# Jetson-CAN-Transceiver.net
KiCad netlist of a schematic drawn in Altium Designer
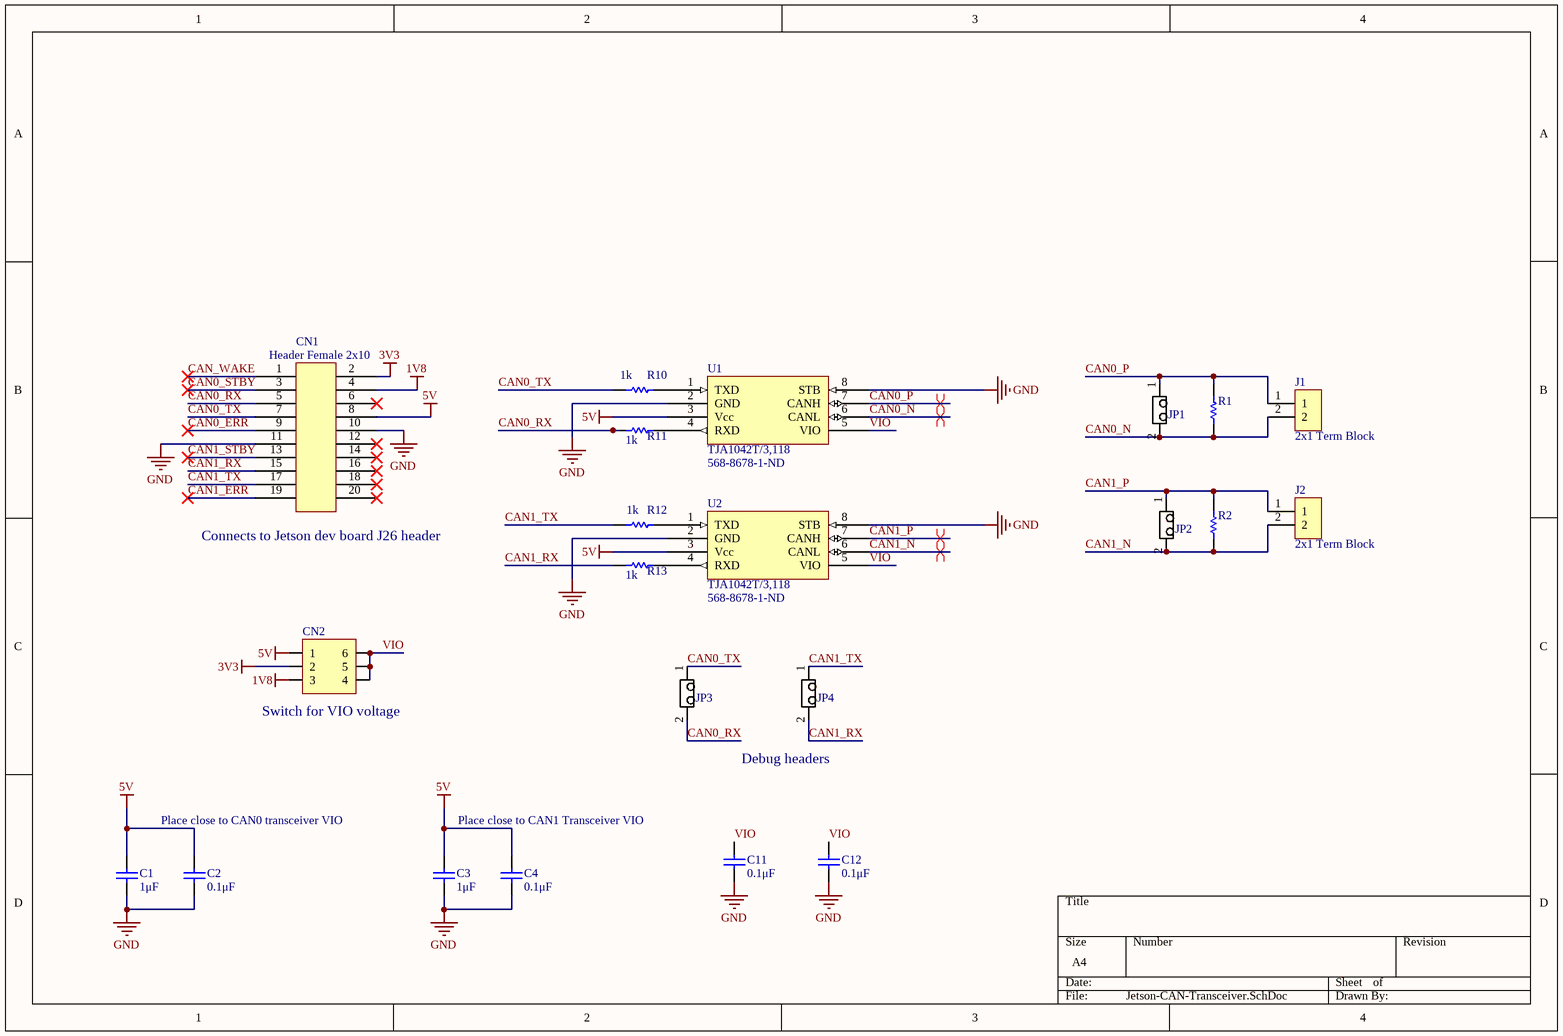
[diagram p0: Jetson-CAN-Transceiver.SchDoc]

(export (version "E")
  (design (tool "Eeschema 10.0.6"))
  (components
    (comp (ref "C1")
      (value "1μF")
      (footprint "CAPC1608N(0603\")")
      (description "Capacitor, Ceramic, 50V, +/- 10%, 0603 SMD, X5R")
      (fields (field (name "CREATED BY") "Lyden Smith"))
      (libsource (lib "AUVic_Integrated_Library_Capacitors") (part "1uF 50V 0603 SMD, Ceramic"))
    )
    (comp (ref "C2")
      (value "0.1μF")
      (footprint "CAPC1608N(0603\")")
      (description "Capacitor, Ceramic, 16V, +/- 10%, 0603 SMD, X7R")
      (fields (field (name "PUBLISHER") "AUVic") (field (name "CREATED BY") "Andy Bates"))
      (libsource (lib "AUVic_Integrated_Library_Capacitors") (part "0.1uF 16V 0603 SMD, Ceramic"))
    )
    (comp (ref "C3")
      (value "1μF")
      (footprint "CAPC1608N(0603\")")
      (description "Capacitor, Ceramic, 50V, +/- 10%, 0603 SMD, X5R")
      (fields (field (name "CREATED BY") "Lyden Smith"))
      (libsource (lib "AUVic_Integrated_Library_Capacitors") (part "1uF 50V 0603 SMD, Ceramic"))
    )
    (comp (ref "C4")
      (value "0.1μF")
      (footprint "CAPC1608N(0603\")")
      (description "Capacitor, Ceramic, 16V, +/- 10%, 0603 SMD, X7R")
      (fields (field (name "PUBLISHER") "AUVic") (field (name "CREATED BY") "Andy Bates"))
      (libsource (lib "AUVic_Integrated_Library_Capacitors") (part "0.1uF 16V 0603 SMD, Ceramic"))
    )
    (comp (ref "C11")
      (value "0.1μF")
      (footprint "CAPC1608N(0603\")")
      (description "Capacitor, Ceramic, 16V, +/- 10%, 0603 SMD, X7R")
      (fields (field (name "PUBLISHER") "AUVic") (field (name "CREATED BY") "Andy Bates"))
      (libsource (lib "AUVic_Integrated_Library_Capacitors") (part "0.1uF 16V 0603 SMD, Ceramic"))
    )
    (comp (ref "C12")
      (value "0.1μF")
      (footprint "CAPC1608N(0603\")")
      (description "Capacitor, Ceramic, 16V, +/- 10%, 0603 SMD, X7R")
      (fields (field (name "PUBLISHER") "AUVic") (field (name "CREATED BY") "Andy Bates"))
      (libsource (lib "AUVic_Integrated_Library_Capacitors") (part "0.1uF 16V 0603 SMD, Ceramic"))
    )
    (comp (ref "CN1")
      (value "Header Female 2x10")
      (footprint "HEADER, FEMALE/MALE, 2x10, 100mil")
      (description "Header, Female with extended Male pins, 2x10, THT, 100mil")
      (fields (field (name "CREATED BY") "Poorna Chander Kalidas"))
      (libsource (lib "AUVic_Integrated_Library_Connectors") (part "Header, Female/Male, 2x10, THT, 100mil"))
    )
    (comp (ref "CN2")
      (value "Header, Male, 2x3, Pitch: 0.1\" (2.54mm), THT")
      (footprint "Header, Male, 2x3, Pitch: 0.1\" (2.54mm),THT")
      (fields
        (field (name "PUBLISHER") "AUVic")
        (field (name "REVIEWED BY") "*")
        (field (name "CREATED BY") "Andy Bates")
      )
      (libsource (lib "AUVic_Integrated_Library_Connectors") (part "Header, Male, 2x3, Pitch{colon} 0.1{dblquote} (2.54mm), THT"))
    )
    (comp (ref "J1")
      (value "2x1 Term Block")
      (footprint "2X1 Terminal Blocks")
      (fields (field (name "MADE BY") "Andy Bates"))
      (libsource (lib "AUVic_Integrated_Library_Connectors") (part "2x1 Terminal Block"))
    )
    (comp (ref "J2")
      (value "2x1 Term Block")
      (footprint "2X1 Terminal Blocks")
      (fields (field (name "MADE BY") "Andy Bates"))
      (libsource (lib "AUVic_Integrated_Library_Connectors") (part "2x1 Terminal Block"))
    )
    (comp (ref "JP1")
      (value "1X2 Pin Head")
      (footprint "2X1 Males Header")
      (fields (field (name "MADE BY") "Andy Bates"))
      (libsource (lib "AUVic_Integrated_Library_Connectors") (part "1x2 Male Header"))
    )
    (comp (ref "JP2")
      (value "1X2 Pin Head")
      (footprint "2X1 Males Header")
      (fields (field (name "MADE BY") "Andy Bates"))
      (libsource (lib "AUVic_Integrated_Library_Connectors") (part "1x2 Male Header"))
    )
    (comp (ref "JP3")
      (value "1X2 Pin Head")
      (footprint "2X1 Males Header")
      (fields (field (name "MADE BY") "Andy Bates"))
      (libsource (lib "AUVic_Integrated_Library_Connectors") (part "1x2 Male Header"))
    )
    (comp (ref "JP4")
      (value "1X2 Pin Head")
      (footprint "2X1 Males Header")
      (fields (field (name "MADE BY") "Andy Bates"))
      (libsource (lib "AUVic_Integrated_Library_Connectors") (part "1x2 Male Header"))
    )
    (comp (ref "R1")
      (value "CRCW0603120KFKEA")
      (footprint "RESC1609X50X30NL10T20")
      (fields (field (name "MANUFACTURER") "Vishay Dale"))
      (libsource (lib "Altium Content Vault") (part "RES"))
    )
    (comp (ref "R2")
      (value "CRCW0603120KFKEA")
      (footprint "RESC1609X50X30NL10T20")
      (fields (field (name "MANUFACTURER") "Vishay Dale"))
      (libsource (lib "Altium Content Vault") (part "RES"))
    )
    (comp (ref "R10")
      (value "1k")
      (footprint "RESC1608N(0603\")")
      (description "1kR, 1%, 1/10W , 0603, SMD")
      (fields (field (name "CREATED BY") "Andy Bates") (field (name "PUBLISHER") "AUVic"))
      (libsource (lib "AUVic_Integrated_Library_Resistors") (part "1kR, 1%, 1/10W , 0603, SMD"))
    )
    (comp (ref "R11")
      (value "1k")
      (footprint "RESC1608N(0603\")")
      (description "1kR, 1%, 1/10W , 0603, SMD")
      (fields (field (name "CREATED BY") "Andy Bates") (field (name "PUBLISHER") "AUVic"))
      (libsource (lib "AUVic_Integrated_Library_Resistors") (part "1kR, 1%, 1/10W , 0603, SMD"))
    )
    (comp (ref "R12")
      (value "1k")
      (footprint "RESC1608N(0603\")")
      (description "1kR, 1%, 1/10W , 0603, SMD")
      (fields (field (name "CREATED BY") "Andy Bates") (field (name "PUBLISHER") "AUVic"))
      (libsource (lib "AUVic_Integrated_Library_Resistors") (part "1kR, 1%, 1/10W , 0603, SMD"))
    )
    (comp (ref "R13")
      (value "1k")
      (footprint "RESC1608N(0603\")")
      (description "1kR, 1%, 1/10W , 0603, SMD")
      (fields (field (name "CREATED BY") "Andy Bates") (field (name "PUBLISHER") "AUVic"))
      (libsource (lib "AUVic_Integrated_Library_Resistors") (part "1kR, 1%, 1/10W , 0603, SMD"))
    )
    (comp (ref "U1")
      (value "TJA1042T/3,118")
      (footprint "8-SOIC")
      (description "1/1 Transceiver Half CANbus 8-SO")
      (fields
        (field (name "SUPPLIER PART NUMBER 1") "568-8678-1-ND")
        (field (name "MADE BY") "Poorna Chander Kalidas")
      )
      (libsource (lib "AUVic_Integrated_Library_Interface") (part "CAN Transceiver"))
    )
    (comp (ref "U2")
      (value "TJA1042T/3,118")
      (footprint "8-SOIC")
      (description "1/1 Transceiver Half CANbus 8-SO")
      (fields
        (field (name "SUPPLIER PART NUMBER 1") "568-8678-1-ND")
        (field (name "MADE BY") "Poorna Chander Kalidas")
      )
      (libsource (lib "AUVic_Integrated_Library_Interface") (part "CAN Transceiver"))
    )
  )
  (nets
    (net (code "1") (name "/CAN0_ERR") (class "Default")
      (node (ref "CN1") (pin "9") (pintype "passive+no_connect"))
    )
    (net (code "2") (name "/CAN0_N") (class "Default")
      (node (ref "J1") (pin "2") (pinfunction "2_2") (pintype "passive"))
      (node (ref "JP1") (pin "2") (pinfunction "2_2") (pintype "passive"))
      (node (ref "R1") (pin "2") (pinfunction "2_2") (pintype "passive"))
      (node (ref "U1") (pin "6") (pinfunction "CANL_6") (pintype "bidirectional"))
    )
    (net (code "3") (name "/CAN0_P") (class "Default")
      (node (ref "J1") (pin "1") (pinfunction "1_1") (pintype "passive"))
      (node (ref "JP1") (pin "1") (pinfunction "1_1") (pintype "passive"))
      (node (ref "R1") (pin "1") (pinfunction "1_1") (pintype "passive"))
      (node (ref "U1") (pin "7") (pinfunction "CANH_7") (pintype "bidirectional"))
    )
    (net (code "4") (name "/CAN0_RX") (class "Default")
      (node (ref "CN1") (pin "5") (pintype "passive"))
      (node (ref "JP3") (pin "2") (pinfunction "2_2") (pintype "passive"))
      (node (ref "R11") (pin "1") (pinfunction "1_1") (pintype "passive"))
    )
    (net (code "5") (name "/CAN0_STBY") (class "Default")
      (node (ref "CN1") (pin "3") (pintype "passive+no_connect"))
    )
    (net (code "6") (name "/CAN0_TX") (class "Default")
      (node (ref "CN1") (pin "7") (pintype "passive"))
      (node (ref "JP3") (pin "1") (pinfunction "1_1") (pintype "passive"))
      (node (ref "R10") (pin "1") (pinfunction "1_1") (pintype "passive"))
    )
    (net (code "7") (name "/CAN1_ERR") (class "Default")
      (node (ref "CN1") (pin "19") (pintype "passive+no_connect"))
    )
    (net (code "8") (name "/CAN1_N") (class "Default")
      (node (ref "J2") (pin "2") (pinfunction "2_2") (pintype "passive"))
      (node (ref "JP2") (pin "2") (pinfunction "2_2") (pintype "passive"))
      (node (ref "R2") (pin "2") (pinfunction "2_2") (pintype "passive"))
      (node (ref "U2") (pin "6") (pinfunction "CANL_6") (pintype "bidirectional"))
    )
    (net (code "9") (name "/CAN1_P") (class "Default")
      (node (ref "J2") (pin "1") (pinfunction "1_1") (pintype "passive"))
      (node (ref "JP2") (pin "1") (pinfunction "1_1") (pintype "passive"))
      (node (ref "R2") (pin "1") (pinfunction "1_1") (pintype "passive"))
      (node (ref "U2") (pin "7") (pinfunction "CANH_7") (pintype "bidirectional"))
    )
    (net (code "10") (name "/CAN1_RX") (class "Default")
      (node (ref "CN1") (pin "15") (pintype "passive"))
      (node (ref "JP4") (pin "2") (pinfunction "2_2") (pintype "passive"))
      (node (ref "R13") (pin "1") (pinfunction "1_1") (pintype "passive"))
    )
    (net (code "11") (name "/CAN1_STBY") (class "Default")
      (node (ref "CN1") (pin "13") (pintype "passive+no_connect"))
    )
    (net (code "12") (name "/CAN1_TX") (class "Default")
      (node (ref "CN1") (pin "17") (pintype "passive"))
      (node (ref "JP4") (pin "1") (pinfunction "1_1") (pintype "passive"))
      (node (ref "R12") (pin "1") (pinfunction "1_1") (pintype "passive"))
    )
    (net (code "13") (name "/CAN_WAKE") (class "Default")
      (node (ref "CN1") (pin "1") (pintype "passive+no_connect"))
    )
    (net (code "14") (name "/VIO") (class "Default")
      (node (ref "C11") (pin "2") (pinfunction "Cathode_2") (pintype "passive"))
      (node (ref "C12") (pin "2") (pinfunction "Cathode_2") (pintype "passive"))
      (node (ref "CN2") (pin "4") (pinfunction "4_4") (pintype "passive"))
      (node (ref "CN2") (pin "5") (pinfunction "5_5") (pintype "passive"))
      (node (ref "CN2") (pin "6") (pinfunction "6_6") (pintype "passive"))
      (node (ref "U1") (pin "5") (pinfunction "VIO_5") (pintype "passive"))
      (node (ref "U2") (pin "5") (pinfunction "VIO_5") (pintype "passive"))
    )
    (net (code "15") (name "1V8") (class "Default")
      (node (ref "CN1") (pin "4") (pintype "passive"))
      (node (ref "CN2") (pin "3") (pinfunction "3_3") (pintype "passive"))
    )
    (net (code "16") (name "3V3") (class "Default")
      (node (ref "CN1") (pin "2") (pintype "passive"))
      (node (ref "CN2") (pin "2") (pinfunction "2_2") (pintype "passive"))
    )
    (net (code "17") (name "5V") (class "Default")
      (node (ref "C1") (pin "2") (pinfunction "Cathode_2") (pintype "passive"))
      (node (ref "C2") (pin "2") (pinfunction "Cathode_2") (pintype "passive"))
      (node (ref "C3") (pin "2") (pinfunction "Cathode_2") (pintype "passive"))
      (node (ref "C4") (pin "2") (pinfunction "Cathode_2") (pintype "passive"))
      (node (ref "CN1") (pin "8") (pintype "passive"))
      (node (ref "CN2") (pin "1") (pinfunction "1_1") (pintype "passive"))
      (node (ref "U1") (pin "3") (pinfunction "Vcc_3") (pintype "power_in"))
      (node (ref "U2") (pin "3") (pinfunction "Vcc_3") (pintype "power_in"))
    )
    (net (code "18") (name "GND") (class "Default")
      (node (ref "C1") (pin "1") (pinfunction "Anode_1") (pintype "passive"))
      (node (ref "C11") (pin "1") (pinfunction "Anode_1") (pintype "passive"))
      (node (ref "C12") (pin "1") (pinfunction "Anode_1") (pintype "passive"))
      (node (ref "C2") (pin "1") (pinfunction "Anode_1") (pintype "passive"))
      (node (ref "C3") (pin "1") (pinfunction "Anode_1") (pintype "passive"))
      (node (ref "C4") (pin "1") (pinfunction "Anode_1") (pintype "passive"))
      (node (ref "CN1") (pin "10") (pintype "passive"))
      (node (ref "CN1") (pin "11") (pintype "passive"))
      (node (ref "U1") (pin "2") (pinfunction "GND_2") (pintype "power_in"))
      (node (ref "U1") (pin "8") (pinfunction "STB_8") (pintype "input"))
      (node (ref "U2") (pin "2") (pinfunction "GND_2") (pintype "power_in"))
      (node (ref "U2") (pin "8") (pinfunction "STB_8") (pintype "input"))
    )
    (net (code "19") (name "Net-(U1-RXD)") (class "Default")
      (node (ref "R11") (pin "2") (pinfunction "2_2") (pintype "passive"))
      (node (ref "U1") (pin "4") (pinfunction "RXD_4") (pintype "output"))
    )
    (net (code "20") (name "Net-(U1-TXD)") (class "Default")
      (node (ref "R10") (pin "2") (pinfunction "2_2") (pintype "passive"))
      (node (ref "U1") (pin "1") (pinfunction "TXD_1") (pintype "input"))
    )
    (net (code "21") (name "Net-(U2-RXD)") (class "Default")
      (node (ref "R13") (pin "2") (pinfunction "2_2") (pintype "passive"))
      (node (ref "U2") (pin "4") (pinfunction "RXD_4") (pintype "output"))
    )
    (net (code "22") (name "Net-(U2-TXD)") (class "Default")
      (node (ref "R12") (pin "2") (pinfunction "2_2") (pintype "passive"))
      (node (ref "U2") (pin "1") (pinfunction "TXD_1") (pintype "input"))
    )
    (net (code "23") (name "unconnected-(CN1-Pad6)") (class "Default")
      (node (ref "CN1") (pin "6") (pintype "passive+no_connect"))
    )
    (net (code "24") (name "unconnected-(CN1-Pad12)") (class "Default")
      (node (ref "CN1") (pin "12") (pintype "passive+no_connect"))
    )
    (net (code "25") (name "unconnected-(CN1-Pad14)") (class "Default")
      (node (ref "CN1") (pin "14") (pintype "passive+no_connect"))
    )
    (net (code "26") (name "unconnected-(CN1-Pad16)") (class "Default")
      (node (ref "CN1") (pin "16") (pintype "passive+no_connect"))
    )
    (net (code "27") (name "unconnected-(CN1-Pad18)") (class "Default")
      (node (ref "CN1") (pin "18") (pintype "passive+no_connect"))
    )
    (net (code "28") (name "unconnected-(CN1-Pad20)") (class "Default")
      (node (ref "CN1") (pin "20") (pintype "passive+no_connect"))
    )
  )
)
